# RiskChemi_Sensors_V2_10.net
KiCad netlist of a schematic drawn in Altium Designer
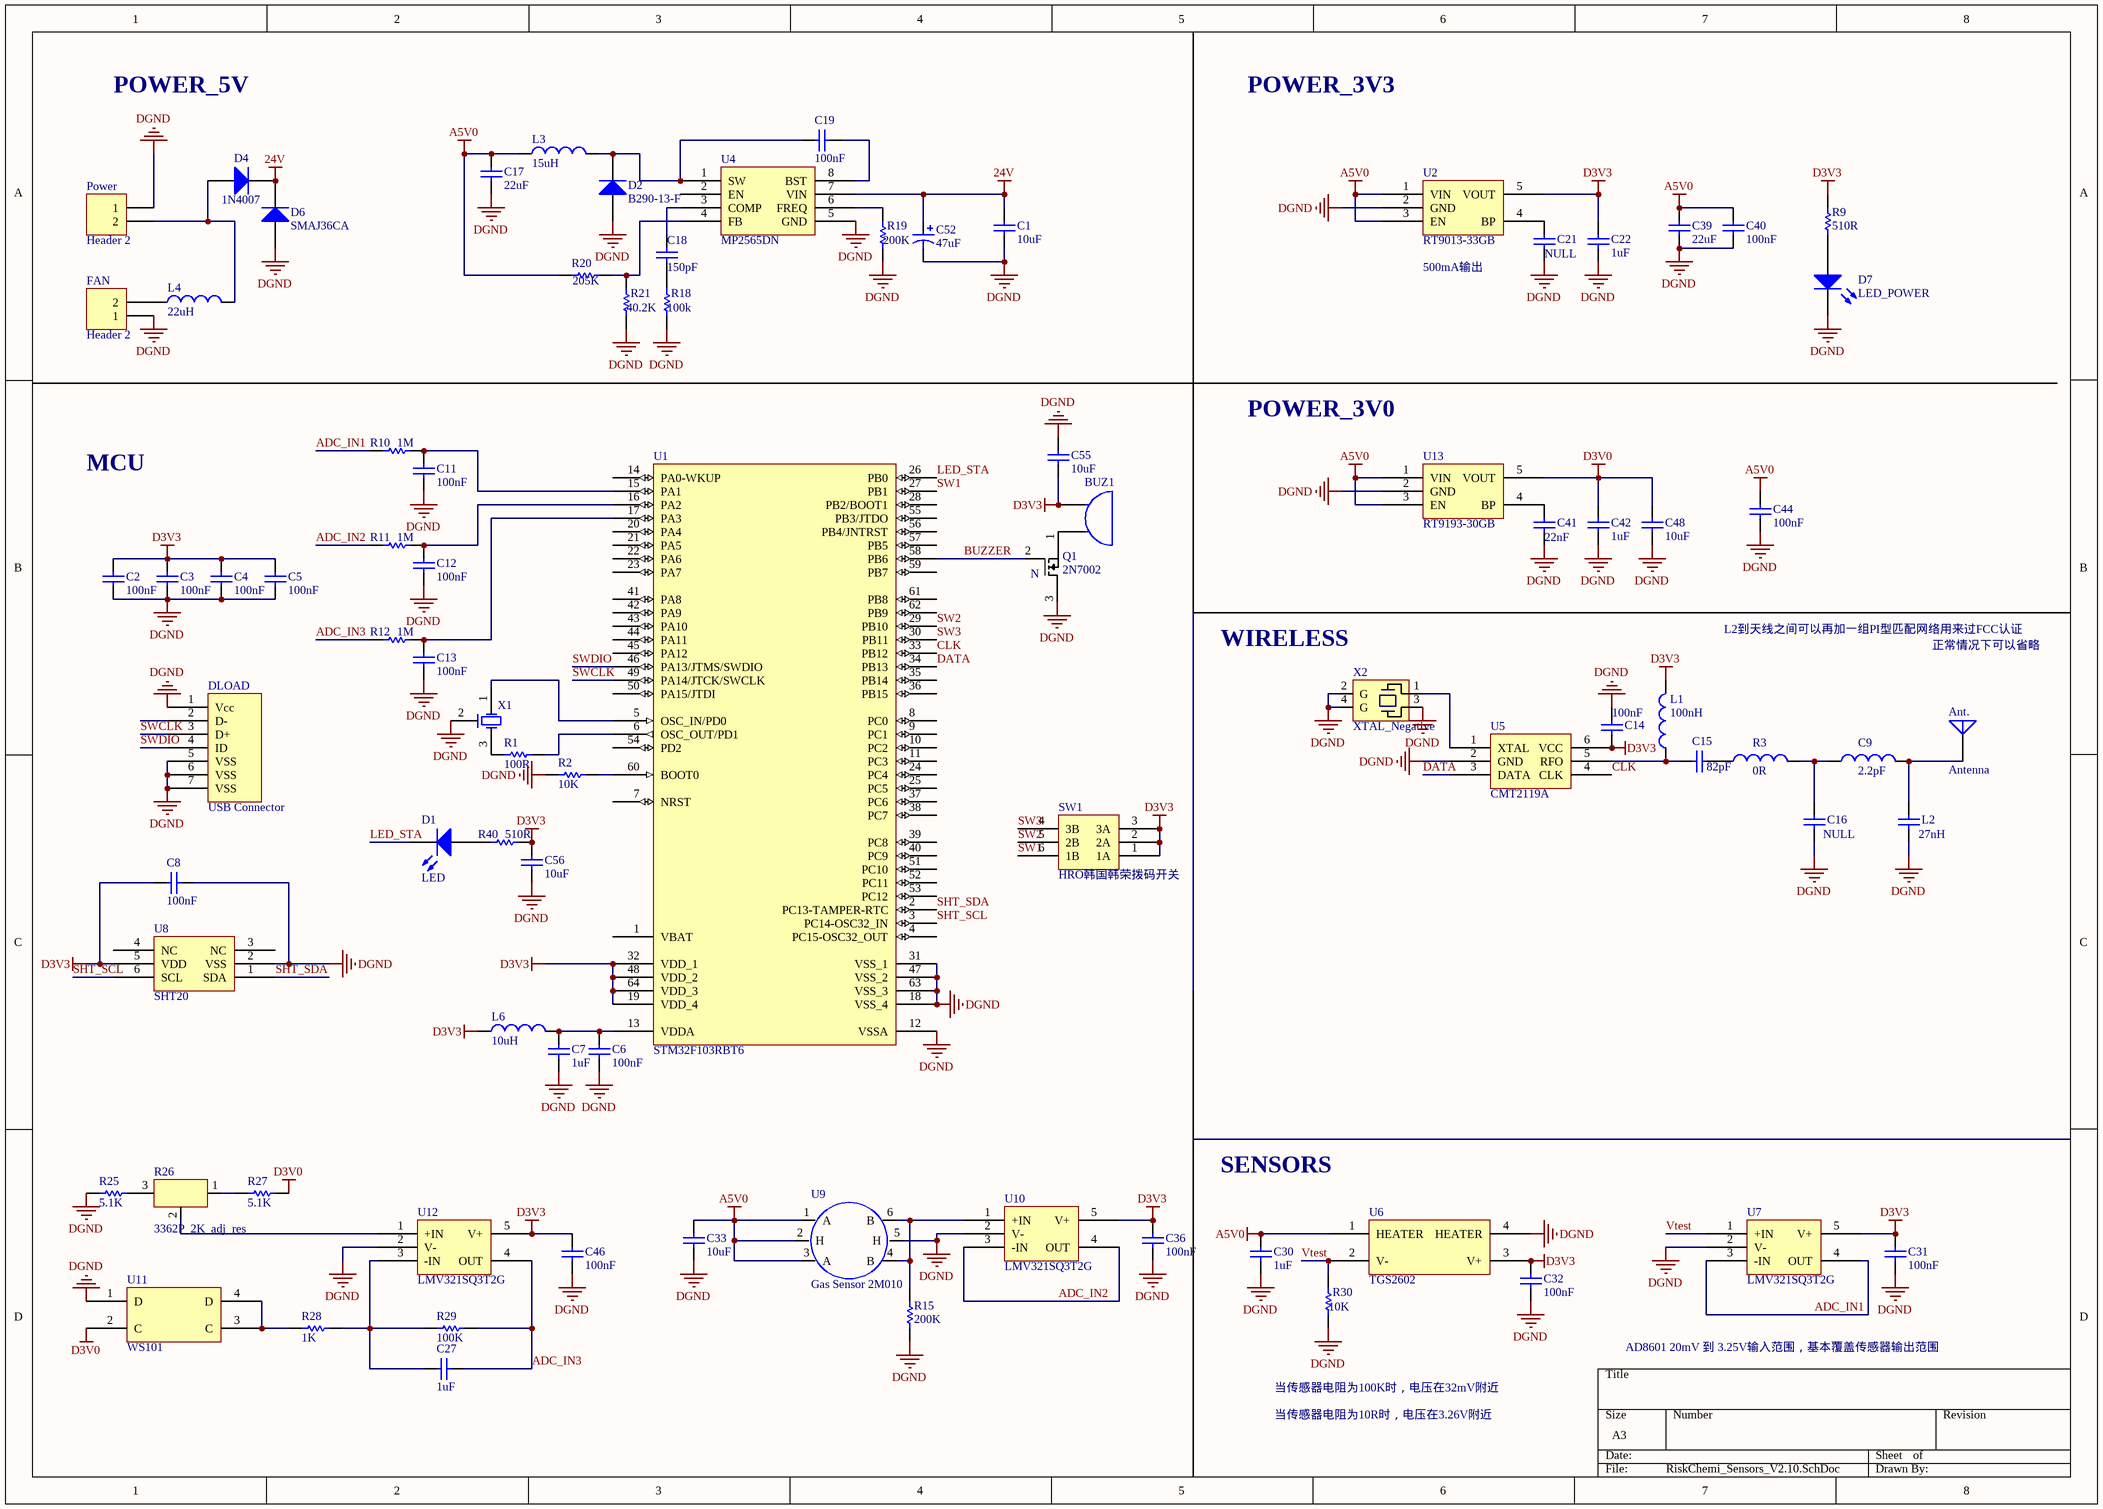
[diagram p0: RiskChemi_Sensors_V2.10.SchDoc]

(export (version "E")
  (design (tool "Eeschema 10.0.6"))
  (components
    (comp (ref "Ant.")
      (value "Antenna")
      (footprint "PIN1")
      (description "Generic Antenna")
      (fields (field (name "PUBLISHER") "Altium Limited"))
      (libsource (lib "Miscellaneous Devices") (part "Antenna"))
    )
    (comp (ref "BUZ1")
      (value "BUZZER 0905 through hole")
      (footprint "BUZ0905")
      (description "Buzzer")
      (libsource (lib "杂元件库") (part "BUZZER"))
    )
    (comp (ref "C1")
      (value "10uF")
      (footprint "0805")
      (description "Capacitor,50V")
      (fields (field (name "PUBLISHER") "Altium Limited"))
      (libsource (lib "Miscellaneous Devices") (part "Cap"))
    )
    (comp (ref "C2")
      (value "100nF")
      (footprint "BinFeng:0603")
      (description "Capacitor")
      (fields (field (name "PUBLISHER") "Altium Limited"))
      (libsource (lib "Miscellaneous Devices") (part "Cap"))
    )
    (comp (ref "C3")
      (value "100nF")
      (footprint "BinFeng:0603")
      (description "Capacitor")
      (fields (field (name "PUBLISHER") "Altium Limited"))
      (libsource (lib "Miscellaneous Devices") (part "Cap"))
    )
    (comp (ref "C4")
      (value "100nF")
      (footprint "BinFeng:0603")
      (description "Capacitor")
      (fields (field (name "PUBLISHER") "Altium Limited"))
      (libsource (lib "Miscellaneous Devices") (part "Cap"))
    )
    (comp (ref "C5")
      (value "100nF")
      (footprint "BinFeng:0603")
      (description "Capacitor")
      (fields (field (name "PUBLISHER") "Altium Limited"))
      (libsource (lib "Miscellaneous Devices") (part "Cap"))
    )
    (comp (ref "C6")
      (value "100nF")
      (footprint "BinFeng:0603")
      (description "Capacitor")
      (fields (field (name "PUBLISHER") "Altium Limited"))
      (libsource (lib "Miscellaneous Devices") (part "Cap"))
    )
    (comp (ref "C7")
      (value "1uF")
      (footprint "BinFeng:0603")
      (description "Capacitor")
      (fields (field (name "PUBLISHER") "Altium Limited"))
      (libsource (lib "Miscellaneous Devices") (part "Cap"))
    )
    (comp (ref "C8")
      (value "100nF")
      (footprint "BinFeng:0603")
      (description "Capacitor")
      (fields (field (name "PUBLISHER") "Altium Limited"))
      (libsource (lib "Miscellaneous Devices") (part "Cap"))
    )
    (comp (ref "C9")
      (value "2.2pF")
      (footprint "0603C")
      (description "Inductor")
      (fields (field (name "PUBLISHER") "Altium Limited"))
      (libsource (lib "Miscellaneous Devices") (part "Inductor"))
    )
    (comp (ref "C11")
      (value "100nF")
      (footprint "BinFeng:0603")
      (description "Capacitor")
      (fields (field (name "PUBLISHER") "Altium Limited"))
      (libsource (lib "Miscellaneous Devices") (part "Cap"))
    )
    (comp (ref "C12")
      (value "100nF")
      (footprint "BinFeng:0603")
      (description "Capacitor")
      (fields (field (name "PUBLISHER") "Altium Limited"))
      (libsource (lib "Miscellaneous Devices") (part "Cap"))
    )
    (comp (ref "C13")
      (value "100nF")
      (footprint "BinFeng:0603")
      (description "Capacitor")
      (fields (field (name "PUBLISHER") "Altium Limited"))
      (libsource (lib "Miscellaneous Devices") (part "Cap"))
    )
    (comp (ref "C14")
      (value "100nF")
      (footprint "BinFeng:0402")
      (description "Capacitor")
      (fields (field (name "PUBLISHER") "Altium Limited"))
      (libsource (lib "Miscellaneous Devices") (part "Cap"))
    )
    (comp (ref "C15")
      (value "82pF")
      (footprint "BinFeng:0402")
      (description "Capacitor")
      (fields (field (name "PUBLISHER") "Altium Limited"))
      (libsource (lib "Miscellaneous Devices") (part "Cap"))
    )
    (comp (ref "C16")
      (value "NULL")
      (footprint "BinFeng:0402")
      (description "Capacitor")
      (fields (field (name "PUBLISHER") "Altium Limited"))
      (libsource (lib "Miscellaneous Devices") (part "Cap"))
    )
    (comp (ref "C17")
      (value "22uF")
      (footprint "0805")
      (description "Capacitor,50V")
      (fields (field (name "PUBLISHER") "Altium Limited"))
      (libsource (lib "Miscellaneous Devices") (part "Cap"))
    )
    (comp (ref "C18")
      (value "150pF")
      (footprint "BinFeng:0603")
      (description "Capacitor")
      (fields (field (name "PUBLISHER") "Altium Limited"))
      (libsource (lib "Miscellaneous Devices") (part "Cap"))
    )
    (comp (ref "C19")
      (value "100nF")
      (footprint "BinFeng:0603")
      (description "Capacitor")
      (fields (field (name "PUBLISHER") "Altium Limited"))
      (libsource (lib "Miscellaneous Devices") (part "Cap"))
    )
    (comp (ref "C21")
      (value "NULL")
      (footprint "BinFeng:0402")
      (description "Capacitor")
      (fields (field (name "PUBLISHER") "Altium Limited"))
      (libsource (lib "Miscellaneous Devices") (part "Cap"))
    )
    (comp (ref "C22")
      (value "1uF")
      (footprint "BinFeng:0402")
      (description "Capacitor")
      (fields (field (name "PUBLISHER") "Altium Limited"))
      (libsource (lib "Miscellaneous Devices") (part "Cap"))
    )
    (comp (ref "C27")
      (value "1uF")
      (footprint "BinFeng:0603")
      (description "Capacitor")
      (fields (field (name "PUBLISHER") "Altium Limited"))
      (libsource (lib "Miscellaneous Devices") (part "Cap"))
    )
    (comp (ref "C30")
      (value "1uF")
      (footprint "BinFeng:0603")
      (description "Capacitor")
      (fields (field (name "PUBLISHER") "Altium Limited"))
      (libsource (lib "Miscellaneous Devices") (part "Cap"))
    )
    (comp (ref "C31")
      (value "100nF")
      (footprint "BinFeng:0603")
      (description "Capacitor")
      (fields (field (name "PUBLISHER") "Altium Limited"))
      (libsource (lib "Miscellaneous Devices") (part "Cap"))
    )
    (comp (ref "C32")
      (value "100nF")
      (footprint "BinFeng:0603")
      (description "Capacitor")
      (fields (field (name "PUBLISHER") "Altium Limited"))
      (libsource (lib "Miscellaneous Devices") (part "Cap"))
    )
    (comp (ref "C33")
      (value "10uF")
      (footprint "0805")
      (description "Capacitor")
      (fields (field (name "PUBLISHER") "Altium Limited"))
      (libsource (lib "Miscellaneous Devices") (part "Cap"))
    )
    (comp (ref "C36")
      (value "100nF")
      (footprint "BinFeng:0603")
      (description "Capacitor")
      (fields (field (name "PUBLISHER") "Altium Limited"))
      (libsource (lib "Miscellaneous Devices") (part "Cap"))
    )
    (comp (ref "C39")
      (value "22uF")
      (footprint "1206")
      (description "Capacitor")
      (fields (field (name "PUBLISHER") "Altium Limited"))
      (libsource (lib "Miscellaneous Devices") (part "Cap"))
    )
    (comp (ref "C40")
      (value "100nF")
      (footprint "BinFeng:0402")
      (description "Capacitor")
      (fields (field (name "PUBLISHER") "Altium Limited"))
      (libsource (lib "Miscellaneous Devices") (part "Cap"))
    )
    (comp (ref "C41")
      (value "22nF")
      (footprint "BinFeng:0402")
      (description "Capacitor")
      (fields (field (name "PUBLISHER") "Altium Limited"))
      (libsource (lib "Miscellaneous Devices") (part "Cap"))
    )
    (comp (ref "C42")
      (value "1uF")
      (footprint "BinFeng:0402")
      (description "Capacitor")
      (fields (field (name "PUBLISHER") "Altium Limited"))
      (libsource (lib "Miscellaneous Devices") (part "Cap"))
    )
    (comp (ref "C44")
      (value "100nF")
      (footprint "BinFeng:0402")
      (description "Capacitor")
      (fields (field (name "PUBLISHER") "Altium Limited"))
      (libsource (lib "Miscellaneous Devices") (part "Cap"))
    )
    (comp (ref "C46")
      (value "100nF")
      (footprint "BinFeng:0603")
      (description "Capacitor")
      (fields (field (name "PUBLISHER") "Altium Limited"))
      (libsource (lib "Miscellaneous Devices") (part "Cap"))
    )
    (comp (ref "C48")
      (value "10uF")
      (footprint "0805")
      (description "Capacitor")
      (fields (field (name "PUBLISHER") "Altium Limited"))
      (libsource (lib "Miscellaneous Devices") (part "Cap"))
    )
    (comp (ref "C52")
      (value "47uF")
      (footprint "cap_pol_8*10.2")
      (description "Polarized Capacitor (Radial)")
      (fields (field (name "PUBLISHER") "Altium Limited"))
      (libsource (lib "Miscellaneous Devices") (part "Cap Pol1"))
    )
    (comp (ref "C55")
      (value "10uF")
      (footprint "0805")
      (description "Capacitor")
      (fields (field (name "PUBLISHER") "Altium Limited"))
      (libsource (lib "Miscellaneous Devices") (part "Cap"))
    )
    (comp (ref "C56")
      (value "10uF")
      (footprint "0805")
      (description "Capacitor")
      (fields (field (name "PUBLISHER") "Altium Limited"))
      (libsource (lib "Miscellaneous Devices") (part "Cap"))
    )
    (comp (ref "D1")
      (value "LED")
      (footprint "1206_LED")
      (description "Typical INFRARED GaAs LED")
      (fields (field (name "PUBLISHER") "Altium Limited"))
      (libsource (lib "Miscellaneous Devices") (part "LED0"))
    )
    (comp (ref "D2")
      (value "B290-13-F")
      (footprint "B290")
      (description "Default Diode")
      (fields (field (name "PUBLISHER") "Altium Limited"))
      (libsource (lib "Miscellaneous Devices") (part "Diode"))
    )
    (comp (ref "D4")
      (value "1N4007")
      (footprint "6032_pol")
      (description "1 Amp General Purpose Rectifier")
      (fields (field (name "PUBLISHER") "Altium Limited"))
      (libsource (lib "Miscellaneous Devices") (part "Diode 1N4007"))
    )
    (comp (ref "D6")
      (value "SMAJ36CA")
      (footprint "B290")
      (description "1 Amp General Purpose Rectifier")
      (fields (field (name "PUBLISHER") "Altium Limited"))
      (libsource (lib "Miscellaneous Devices") (part "Diode 1N4007"))
    )
    (comp (ref "D7")
      (value "LED_POWER")
      (footprint "1206_LED")
      (description "Typical INFRARED GaAs LED")
      (fields (field (name "PUBLISHER") "Altium Limited"))
      (libsource (lib "Miscellaneous Devices") (part "LED0"))
    )
    (comp (ref "DLOAD")
      (value "USB Connector")
      (footprint "Mini_USB")
      (libsource (lib "BinFeng_Connectors") (part "Component_1"))
    )
    (comp (ref "FAN")
      (value "Header 2")
      (footprint "HDR1X2")
      (description "Header, 2-Pin")
      (fields (field (name "PUBLISHER") "Altium Limited"))
      (libsource (lib "Miscellaneous Connectors") (part "Header 2"))
    )
    (comp (ref "L1")
      (value "100nH")
      (footprint "0603C")
      (description "Inductor")
      (fields (field (name "PUBLISHER") "Altium Limited"))
      (libsource (lib "Miscellaneous Devices") (part "Inductor"))
    )
    (comp (ref "L2")
      (value "27nH")
      (footprint "BinFeng:0402")
      (description "Capacitor")
      (fields (field (name "PUBLISHER") "Altium Limited"))
      (libsource (lib "Miscellaneous Devices") (part "Cap"))
    )
    (comp (ref "L3")
      (value "15uH")
      (footprint "4*4 Inductor")
      (description "Inductor, 1A")
      (fields (field (name "PUBLISHER") "Altium Limited"))
      (libsource (lib "Miscellaneous Devices") (part "Inductor"))
    )
    (comp (ref "L4")
      (value "22uH")
      (footprint "10*10Inductor")
      (description "Inductor, 1A")
      (fields (field (name "PUBLISHER") "Altium Limited"))
      (libsource (lib "Miscellaneous Devices") (part "Inductor"))
    )
    (comp (ref "L6")
      (value "10uH")
      (footprint "0805")
      (description "Inductor")
      (fields (field (name "PUBLISHER") "Altium Limited"))
      (libsource (lib "Miscellaneous Devices") (part "Inductor"))
    )
    (comp (ref "Power")
      (value "Header 2")
      (footprint "HDR1X2")
      (description "Header, 2-Pin")
      (fields (field (name "PUBLISHER") "Altium Limited"))
      (libsource (lib "") (part "Header 2_1"))
    )
    (comp (ref "Q1") (value "2N7002") (footprint "2N7002") (libsource (lib "seeder") (part "N-MOSFET")))
    (comp (ref "R1")
      (value "100R")
      (footprint "BinFeng:0603")
      (description "Resistor")
      (fields (field (name "PUBLISHER") "Altium Limited"))
      (libsource (lib "Miscellaneous Devices") (part "Res1"))
    )
    (comp (ref "R2")
      (value "10K")
      (footprint "BinFeng:0603")
      (description "Resistor")
      (fields (field (name "PUBLISHER") "Altium Limited"))
      (libsource (lib "Miscellaneous Devices") (part "Res1"))
    )
    (comp (ref "R3")
      (value "0R")
      (footprint "0603C")
      (description "Inductor")
      (fields (field (name "PUBLISHER") "Altium Limited"))
      (libsource (lib "Miscellaneous Devices") (part "Inductor"))
    )
    (comp (ref "R9")
      (value "510R")
      (footprint "BinFeng:0603")
      (description "Resistor")
      (fields (field (name "PUBLISHER") "Altium Limited"))
      (libsource (lib "Miscellaneous Devices") (part "Res1"))
    )
    (comp (ref "R10")
      (value "1M")
      (footprint "BinFeng:0603")
      (description "Resistor")
      (fields (field (name "PUBLISHER") "Altium Limited"))
      (libsource (lib "Miscellaneous Devices") (part "Res1"))
    )
    (comp (ref "R11")
      (value "1M")
      (footprint "BinFeng:0603")
      (description "Resistor")
      (fields (field (name "PUBLISHER") "Altium Limited"))
      (libsource (lib "Miscellaneous Devices") (part "Res1"))
    )
    (comp (ref "R12")
      (value "1M")
      (footprint "BinFeng:0603")
      (description "Resistor")
      (fields (field (name "PUBLISHER") "Altium Limited"))
      (libsource (lib "Miscellaneous Devices") (part "Res1"))
    )
    (comp (ref "R15")
      (value "200K")
      (footprint "BinFeng:0603C")
      (description "Resistor")
      (fields (field (name "Comment") "Res1") (field (name "PUBLISHER") "Altium Limited"))
      (libsource (lib "Miscellaneous Devices") (part "Res1"))
    )
    (comp (ref "R18")
      (value "100k")
      (footprint "BinFeng:0603")
      (description "Resistor")
      (fields (field (name "PUBLISHER") "Altium Limited"))
      (libsource (lib "Miscellaneous Devices") (part "Res1"))
    )
    (comp (ref "R19")
      (value "200K")
      (footprint "BinFeng:0402")
      (description "Resistor")
      (fields (field (name "PUBLISHER") "Altium Limited"))
      (libsource (lib "Miscellaneous Devices") (part "Res1"))
    )
    (comp (ref "R20")
      (value "205K")
      (footprint "BinFeng:0603")
      (description "Resistor")
      (fields (field (name "PUBLISHER") "Altium Limited"))
      (libsource (lib "Miscellaneous Devices") (part "Res1"))
    )
    (comp (ref "R21")
      (value "40.2K")
      (footprint "BinFeng:0603")
      (description "Resistor")
      (fields (field (name "PUBLISHER") "Altium Limited"))
      (libsource (lib "Miscellaneous Devices") (part "Res1"))
    )
    (comp (ref "R25")
      (value "5.1K")
      (footprint "BinFeng:0603")
      (description "Resistor")
      (fields (field (name "PUBLISHER") "Altium Limited"))
      (libsource (lib "Miscellaneous Devices") (part "Res1"))
    )
    (comp (ref "R26")
      (value "3362P_2K_adj_res")
      (footprint "res_adj")
      (libsource (lib "BinFeng_IC") (part "res_adj"))
    )
    (comp (ref "R27")
      (value "5.1K")
      (footprint "BinFeng:0603")
      (description "Resistor")
      (fields (field (name "PUBLISHER") "Altium Limited"))
      (libsource (lib "Miscellaneous Devices") (part "Res1"))
    )
    (comp (ref "R28")
      (value "1K")
      (footprint "BinFeng:0603")
      (description "Resistor")
      (fields (field (name "PUBLISHER") "Altium Limited"))
      (libsource (lib "Miscellaneous Devices") (part "Res1"))
    )
    (comp (ref "R29")
      (value "100K")
      (footprint "BinFeng:0603")
      (description "Resistor")
      (fields (field (name "PUBLISHER") "Altium Limited"))
      (libsource (lib "Miscellaneous Devices") (part "Res1"))
    )
    (comp (ref "R30")
      (value "10K")
      (footprint "BinFeng:0603")
      (description "Resistor")
      (fields (field (name "PUBLISHER") "Altium Limited"))
      (libsource (lib "Miscellaneous Devices") (part "Res1"))
    )
    (comp (ref "R40")
      (value "510R")
      (footprint "BinFeng:0603")
      (description "Resistor")
      (fields (field (name "PUBLISHER") "Altium Limited"))
      (libsource (lib "Miscellaneous Devices") (part "Res1"))
    )
    (comp (ref "SW1")
      (value "HRO韩国韩荣拨码开关")
      (footprint "SW_6P_HRO")
      (libsource (lib "BinFeng_IC") (part "SW_6P"))
    )
    (comp (ref "U1")
      (value "STM32F103RBT6")
      (footprint "LQFP64_N")
      (description "STM32 ARM-based 32-bit MCU with 64 Kbytes Flash, 64-pin LQFP, Industrial Temperature")
      (fields (field (name "PUBLISHER") "Altium Limited"))
      (libsource (lib "ST Microcontroller 32-Bit STM32") (part "STM32F103R8T6"))
    )
    (comp (ref "U2")
      (value "RT9013-33GB")
      (footprint "SOT-23-5")
      (libsource (lib "BinFeng_IC") (part "RT9193"))
    )
    (comp (ref "U4")
      (value "MP2565DN")
      (footprint "so-8")
      (description "DCDC 4.5V~28V input 1.8V ~5V output low power")
      (libsource (lib "BinFeng_IC") (part "MP1584"))
    )
    (comp (ref "U5")
      (value "CMT2119A")
      (footprint "sot23-6")
      (libsource (lib "BinFeng_IC") (part "CMT2119A"))
    )
    (comp (ref "U6")
      (value "TGS2602")
      (footprint "Gas Sensor TGS2602 Slot")
      (description "VOC sensor")
      (libsource (lib "BinFeng_IC") (part "TGS2602"))
    )
    (comp (ref "U7")
      (value "LMV321SQ3T2G")
      (footprint "SC-70-5")
      (libsource (lib "BinFeng_IC") (part "LMV321SQ3T2G"))
    )
    (comp (ref "U8") (value "SHT20") (footprint "SHT20") (libsource (lib "BinFeng_IC") (part "SHT20")))
    (comp (ref "U9")
      (value "Gas Sensor 2M010")
      (footprint "Gas Sensor 2M010 Slot")
      (libsource (lib "BinFeng_IC") (part "Gas Sensor"))
    )
    (comp (ref "U10")
      (value "LMV321SQ3T2G")
      (footprint "SC-70-5")
      (libsource (lib "BinFeng_IC") (part "LMV321SQ3T2G"))
    )
    (comp (ref "U11")
      (value "WS101")
      (footprint "Gas_Sensor_WS101_Slot")
      (libsource (lib "BinFeng_IC") (part "Gas Sensor_WS101"))
    )
    (comp (ref "U12")
      (value "LMV321SQ3T2G")
      (footprint "SC-70-5")
      (libsource (lib "BinFeng_IC") (part "LMV321SQ3T2G"))
    )
    (comp (ref "U13")
      (value "RT9193-30GB")
      (footprint "SOT-23-5")
      (libsource (lib "BinFeng_IC") (part "RT9193"))
    )
    (comp (ref "X1") (value "8M smd") (footprint "8Mhz_XTAL") (libsource (lib "Schlib1") (part "8M smd")))
    (comp (ref "X2")
      (value "XTAL_Negative")
      (footprint "XTAL3225")
      (libsource (lib "BinFeng_IC") (part "XTAL_Negative"))
    )
  )
  (nets
    (net (code "1") (name "/ADC_IN1") (class "Default")
      (node (ref "R10") (pin "1") (pinfunction "1_1") (pintype "passive"))
      (node (ref "U7") (pin "3") (pinfunction "-IN_3") (pintype "passive"))
      (node (ref "U7") (pin "4") (pinfunction "OUT_4") (pintype "passive"))
    )
    (net (code "2") (name "/ADC_IN2") (class "Default")
      (node (ref "R11") (pin "1") (pinfunction "1_1") (pintype "passive"))
      (node (ref "U10") (pin "3") (pinfunction "-IN_3") (pintype "passive"))
      (node (ref "U10") (pin "4") (pinfunction "OUT_4") (pintype "passive"))
    )
    (net (code "3") (name "/ADC_IN3") (class "Default")
      (node (ref "C27") (pin "1") (pinfunction "1_1") (pintype "passive"))
      (node (ref "R12") (pin "1") (pinfunction "1_1") (pintype "passive"))
      (node (ref "R29") (pin "2") (pinfunction "2_2") (pintype "passive"))
      (node (ref "U12") (pin "4") (pinfunction "OUT_4") (pintype "passive"))
    )
    (net (code "4") (name "/BUZZER") (class "Default")
      (node (ref "Q1") (pin "2") (pinfunction "G_2") (pintype "passive"))
      (node (ref "U1") (pin "58") (pinfunction "PB6_58") (pintype "bidirectional"))
    )
    (net (code "5") (name "/CLK") (class "Default")
      (node (ref "U1") (pin "33") (pinfunction "PB12_33") (pintype "bidirectional"))
      (node (ref "U5") (pin "4") (pinfunction "CLK_4") (pintype "passive"))
    )
    (net (code "6") (name "/DATA") (class "Default")
      (node (ref "U1") (pin "34") (pinfunction "PB13_34") (pintype "bidirectional"))
      (node (ref "U5") (pin "3") (pinfunction "DATA_3") (pintype "passive"))
    )
    (net (code "7") (name "/LED_STA") (class "Default")
      (node (ref "D1") (pin "2") (pinfunction "K_2") (pintype "passive"))
      (node (ref "U1") (pin "26") (pinfunction "PB0_26") (pintype "bidirectional"))
    )
    (net (code "8") (name "/SHT_SCL") (class "Default")
      (node (ref "U1") (pin "3") (pinfunction "PC14-OSC32_IN_3") (pintype "bidirectional"))
      (node (ref "U8") (pin "6") (pinfunction "SCL_6") (pintype "passive"))
    )
    (net (code "9") (name "/SHT_SDA") (class "Default")
      (node (ref "U1") (pin "2") (pinfunction "PC13-TAMPER-RTC_2") (pintype "bidirectional"))
      (node (ref "U8") (pin "1") (pinfunction "SDA_1") (pintype "passive"))
    )
    (net (code "10") (name "/SW1") (class "Default")
      (node (ref "SW1") (pin "6") (pinfunction "1B_6") (pintype "passive"))
      (node (ref "U1") (pin "27") (pinfunction "PB1_27") (pintype "bidirectional"))
    )
    (net (code "11") (name "/SW2") (class "Default")
      (node (ref "SW1") (pin "5") (pinfunction "2B_5") (pintype "passive"))
      (node (ref "U1") (pin "29") (pinfunction "PB10_29") (pintype "bidirectional"))
    )
    (net (code "12") (name "/SW3") (class "Default")
      (node (ref "SW1") (pin "4") (pinfunction "3B_4") (pintype "passive"))
      (node (ref "U1") (pin "30") (pinfunction "PB11_30") (pintype "bidirectional"))
    )
    (net (code "13") (name "/SWCLK") (class "Default")
      (node (ref "DLOAD") (pin "3") (pinfunction "D+_3") (pintype "passive"))
      (node (ref "U1") (pin "49") (pinfunction "PA14/JTCK/SWCLK_49") (pintype "bidirectional"))
    )
    (net (code "14") (name "/SWDIO") (class "Default")
      (node (ref "DLOAD") (pin "4") (pinfunction "ID_4") (pintype "passive"))
      (node (ref "U1") (pin "46") (pinfunction "PA13/JTMS/SWDIO_46") (pintype "bidirectional"))
    )
    (net (code "15") (name "/Vtest") (class "Default")
      (node (ref "R30") (pin "2") (pinfunction "2_2") (pintype "passive"))
      (node (ref "U6") (pin "2") (pinfunction "V-_2") (pintype "passive"))
      (node (ref "U7") (pin "1") (pinfunction "+IN_1") (pintype "passive"))
    )
    (net (code "16") (name "24V") (class "Default")
      (node (ref "C1") (pin "2") (pinfunction "2_2") (pintype "passive"))
      (node (ref "C52") (pin "1") (pinfunction "1_1") (pintype "passive"))
      (node (ref "D4") (pin "2") (pinfunction "K_2") (pintype "passive"))
      (node (ref "D6") (pin "2") (pinfunction "K_2") (pintype "passive"))
      (node (ref "U4") (pin "7") (pinfunction "VIN_7") (pintype "passive"))
    )
    (net (code "17") (name "A5V0") (class "Default")
      (node (ref "C17") (pin "2") (pinfunction "2_2") (pintype "passive"))
      (node (ref "C30") (pin "2") (pinfunction "2_2") (pintype "passive"))
      (node (ref "C33") (pin "2") (pinfunction "2_2") (pintype "passive"))
      (node (ref "C39") (pin "1") (pinfunction "1_1") (pintype "passive"))
      (node (ref "C40") (pin "2") (pinfunction "2_2") (pintype "passive"))
      (node (ref "C44") (pin "2") (pinfunction "2_2") (pintype "passive"))
      (node (ref "L3") (pin "1") (pinfunction "1_1") (pintype "passive"))
      (node (ref "R20") (pin "2") (pinfunction "2_2") (pintype "passive"))
      (node (ref "U13") (pin "1") (pinfunction "VIN_1") (pintype "passive"))
      (node (ref "U13") (pin "3") (pinfunction "EN_3") (pintype "passive"))
      (node (ref "U2") (pin "1") (pinfunction "VIN_1") (pintype "passive"))
      (node (ref "U2") (pin "3") (pinfunction "EN_3") (pintype "passive"))
      (node (ref "U6") (pin "1") (pinfunction "HEATER_1") (pintype "passive"))
      (node (ref "U9") (pin "1") (pinfunction "A_1") (pintype "passive"))
      (node (ref "U9") (pin "2") (pinfunction "H_2") (pintype "passive"))
      (node (ref "U9") (pin "3") (pinfunction "A_3") (pintype "passive"))
    )
    (net (code "18") (name "D3V0") (class "Default")
      (node (ref "C42") (pin "2") (pinfunction "2_2") (pintype "passive"))
      (node (ref "C48") (pin "2") (pinfunction "2_2") (pintype "passive"))
      (node (ref "R27") (pin "2") (pinfunction "2_2") (pintype "passive"))
      (node (ref "U11") (pin "2") (pinfunction "C_2") (pintype "passive"))
      (node (ref "U13") (pin "5") (pinfunction "VOUT_5") (pintype "passive"))
    )
    (net (code "19") (name "D3V3") (class "Default")
      (node (ref "BUZ1") (pin "1") (pinfunction "A_1") (pintype "passive"))
      (node (ref "C14") (pin "2") (pinfunction "2_2") (pintype "passive"))
      (node (ref "C2") (pin "2") (pinfunction "2_2") (pintype "passive"))
      (node (ref "C22") (pin "2") (pinfunction "2_2") (pintype "passive"))
      (node (ref "C3") (pin "2") (pinfunction "2_2") (pintype "passive"))
      (node (ref "C31") (pin "2") (pinfunction "2_2") (pintype "passive"))
      (node (ref "C32") (pin "2") (pinfunction "2_2") (pintype "passive"))
      (node (ref "C36") (pin "2") (pinfunction "2_2") (pintype "passive"))
      (node (ref "C4") (pin "2") (pinfunction "2_2") (pintype "passive"))
      (node (ref "C46") (pin "2") (pinfunction "2_2") (pintype "passive"))
      (node (ref "C5") (pin "2") (pinfunction "2_2") (pintype "passive"))
      (node (ref "C55") (pin "2") (pinfunction "2_2") (pintype "passive"))
      (node (ref "C56") (pin "2") (pinfunction "2_2") (pintype "passive"))
      (node (ref "C8") (pin "2") (pinfunction "2_2") (pintype "passive"))
      (node (ref "L1") (pin "2") (pinfunction "2_2") (pintype "passive"))
      (node (ref "L6") (pin "1") (pinfunction "1_1") (pintype "passive"))
      (node (ref "R40") (pin "2") (pinfunction "2_2") (pintype "passive"))
      (node (ref "R9") (pin "2") (pinfunction "2_2") (pintype "passive"))
      (node (ref "SW1") (pin "1") (pinfunction "1A_1") (pintype "passive"))
      (node (ref "SW1") (pin "2") (pinfunction "2A_2") (pintype "passive"))
      (node (ref "SW1") (pin "3") (pinfunction "3A_3") (pintype "passive"))
      (node (ref "U1") (pin "19") (pinfunction "VDD_4_19") (pintype "power_in"))
      (node (ref "U1") (pin "32") (pinfunction "VDD_1_32") (pintype "power_in"))
      (node (ref "U1") (pin "48") (pinfunction "VDD_2_48") (pintype "power_in"))
      (node (ref "U1") (pin "64") (pinfunction "VDD_3_64") (pintype "power_in"))
      (node (ref "U10") (pin "5") (pinfunction "V+_5") (pintype "passive"))
      (node (ref "U12") (pin "5") (pinfunction "V+_5") (pintype "passive"))
      (node (ref "U2") (pin "5") (pinfunction "VOUT_5") (pintype "passive"))
      (node (ref "U5") (pin "6") (pinfunction "VCC_6") (pintype "passive"))
      (node (ref "U6") (pin "3") (pinfunction "V+_3") (pintype "passive"))
      (node (ref "U7") (pin "5") (pinfunction "V+_5") (pintype "passive"))
      (node (ref "U8") (pin "5") (pinfunction "VDD_5") (pintype "passive"))
    )
    (net (code "20") (name "DGND") (class "Default")
      (node (ref "C1") (pin "1") (pinfunction "1_1") (pintype "passive"))
      (node (ref "C11") (pin "2") (pinfunction "2_2") (pintype "passive"))
      (node (ref "C12") (pin "1") (pinfunction "1_1") (pintype "passive"))
      (node (ref "C13") (pin "1") (pinfunction "1_1") (pintype "passive"))
      (node (ref "C14") (pin "1") (pinfunction "1_1") (pintype "passive"))
      (node (ref "C16") (pin "1") (pinfunction "1_1") (pintype "passive"))
      (node (ref "C17") (pin "1") (pinfunction "1_1") (pintype "passive"))
      (node (ref "C2") (pin "1") (pinfunction "1_1") (pintype "passive"))
      (node (ref "C21") (pin "1") (pinfunction "1_1") (pintype "passive"))
      (node (ref "C22") (pin "1") (pinfunction "1_1") (pintype "passive"))
      (node (ref "C3") (pin "1") (pinfunction "1_1") (pintype "passive"))
      (node (ref "C30") (pin "1") (pinfunction "1_1") (pintype "passive"))
      (node (ref "C31") (pin "1") (pinfunction "1_1") (pintype "passive"))
      (node (ref "C32") (pin "1") (pinfunction "1_1") (pintype "passive"))
      (node (ref "C33") (pin "1") (pinfunction "1_1") (pintype "passive"))
      (node (ref "C36") (pin "1") (pinfunction "1_1") (pintype "passive"))
      (node (ref "C39") (pin "2") (pinfunction "2_2") (pintype "passive"))
      (node (ref "C4") (pin "1") (pinfunction "1_1") (pintype "passive"))
      (node (ref "C40") (pin "1") (pinfunction "1_1") (pintype "passive"))
      (node (ref "C41") (pin "1") (pinfunction "1_1") (pintype "passive"))
      (node (ref "C42") (pin "1") (pinfunction "1_1") (pintype "passive"))
      (node (ref "C44") (pin "1") (pinfunction "1_1") (pintype "passive"))
      (node (ref "C46") (pin "1") (pinfunction "1_1") (pintype "passive"))
      (node (ref "C48") (pin "1") (pinfunction "1_1") (pintype "passive"))
      (node (ref "C5") (pin "1") (pinfunction "1_1") (pintype "passive"))
      (node (ref "C52") (pin "2") (pinfunction "2_2") (pintype "passive"))
      (node (ref "C55") (pin "1") (pinfunction "1_1") (pintype "passive"))
      (node (ref "C56") (pin "1") (pinfunction "1_1") (pintype "passive"))
      (node (ref "C6") (pin "1") (pinfunction "1_1") (pintype "passive"))
      (node (ref "C7") (pin "1") (pinfunction "1_1") (pintype "passive"))
      (node (ref "C8") (pin "1") (pinfunction "1_1") (pintype "passive"))
      (node (ref "D2") (pin "1") (pinfunction "A_1") (pintype "passive"))
      (node (ref "D6") (pin "1") (pinfunction "A_1") (pintype "passive"))
      (node (ref "D7") (pin "2") (pinfunction "K_2") (pintype "passive"))
      (node (ref "DLOAD") (pin "1") (pinfunction "Vcc_1") (pintype "passive"))
      (node (ref "DLOAD") (pin "5") (pinfunction "VSS_5") (pintype "passive"))
      (node (ref "DLOAD") (pin "6") (pinfunction "VSS_6") (pintype "passive"))
      (node (ref "DLOAD") (pin "7") (pinfunction "VSS_7") (pintype "passive"))
      (node (ref "FAN") (pin "1") (pinfunction "1_1") (pintype "passive"))
      (node (ref "L2") (pin "1") (pinfunction "1_1") (pintype "passive"))
      (node (ref "Power") (pin "1") (pinfunction "1_1") (pintype "passive"))
      (node (ref "Q1") (pin "3") (pinfunction "S_3") (pintype "passive"))
      (node (ref "R15") (pin "2") (pinfunction "2_2") (pintype "passive"))
      (node (ref "R18") (pin "1") (pinfunction "1_1") (pintype "passive"))
      (node (ref "R19") (pin "1") (pinfunction "1_1") (pintype "passive"))
      (node (ref "R2") (pin "1") (pinfunction "1_1") (pintype "passive"))
      (node (ref "R21") (pin "1") (pinfunction "1_1") (pintype "passive"))
      (node (ref "R25") (pin "1") (pinfunction "1_1") (pintype "passive"))
      (node (ref "R30") (pin "1") (pinfunction "1_1") (pintype "passive"))
      (node (ref "U1") (pin "12") (pinfunction "VSSA_12") (pintype "power_in"))
      (node (ref "U1") (pin "18") (pinfunction "VSS_4_18") (pintype "power_in"))
      (node (ref "U1") (pin "31") (pinfunction "VSS_1_31") (pintype "power_in"))
      (node (ref "U1") (pin "47") (pinfunction "VSS_2_47") (pintype "power_in"))
      (node (ref "U1") (pin "63") (pinfunction "VSS_3_63") (pintype "power_in"))
      (node (ref "U10") (pin "2") (pinfunction "V-_2") (pintype "passive"))
      (node (ref "U11") (pin "1") (pinfunction "D_1") (pintype "passive"))
      (node (ref "U12") (pin "2") (pinfunction "V-_2") (pintype "passive"))
      (node (ref "U13") (pin "2") (pinfunction "GND_2") (pintype "passive"))
      (node (ref "U2") (pin "2") (pinfunction "GND_2") (pintype "passive"))
      (node (ref "U4") (pin "5") (pinfunction "GND_5") (pintype "passive"))
      (node (ref "U5") (pin "2") (pinfunction "GND_2") (pintype "passive"))
      (node (ref "U6") (pin "4") (pinfunction "HEATER_4") (pintype "passive"))
      (node (ref "U7") (pin "2") (pinfunction "V-_2") (pintype "passive"))
      (node (ref "U8") (pin "2") (pinfunction "VSS_2") (pintype "passive"))
      (node (ref "U9") (pin "5") (pinfunction "H_5") (pintype "passive"))
      (node (ref "X1") (pin "2") (pinfunction "GND_2") (pintype "passive"))
      (node (ref "X2") (pin "2") (pinfunction "G_2") (pintype "passive"))
      (node (ref "X2") (pin "3") (pintype "passive"))
      (node (ref "X2") (pin "4") (pinfunction "G_4") (pintype "passive"))
    )
    (net (code "21") (name "Net-(Ant.-A)") (class "Default")
      (node (ref "Ant.") (pin "1") (pinfunction "A_1") (pintype "passive"))
      (node (ref "C9") (pin "2") (pinfunction "2_2") (pintype "passive"))
      (node (ref "L2") (pin "2") (pinfunction "2_2") (pintype "passive"))
    )
    (net (code "22") (name "Net-(BUZ1-B)") (class "Default")
      (node (ref "BUZ1") (pin "2") (pinfunction "B_2") (pintype "passive"))
      (node (ref "Q1") (pin "1") (pinfunction "D_1") (pintype "passive"))
    )
    (net (code "23") (name "Net-(C15-Pad2)") (class "Default")
      (node (ref "C15") (pin "2") (pinfunction "2_2") (pintype "passive"))
      (node (ref "R3") (pin "1") (pinfunction "1_1") (pintype "passive"))
    )
    (net (code "24") (name "Net-(C16-Pad2)") (class "Default")
      (node (ref "C16") (pin "2") (pinfunction "2_2") (pintype "passive"))
      (node (ref "C9") (pin "1") (pinfunction "1_1") (pintype "passive"))
      (node (ref "R3") (pin "2") (pinfunction "2_2") (pintype "passive"))
    )
    (net (code "25") (name "Net-(C18-Pad2)") (class "Default")
      (node (ref "C18") (pin "2") (pinfunction "2_2") (pintype "passive"))
      (node (ref "R18") (pin "2") (pinfunction "2_2") (pintype "passive"))
    )
    (net (code "26") (name "Net-(D1-A)") (class "Default")
      (node (ref "D1") (pin "1") (pinfunction "A_1") (pintype "passive"))
      (node (ref "R40") (pin "1") (pinfunction "1_1") (pintype "passive"))
    )
    (net (code "27") (name "Net-(D2-K)") (class "Default")
      (node (ref "C19") (pin "2") (pinfunction "2_2") (pintype "passive"))
      (node (ref "D2") (pin "2") (pinfunction "K_2") (pintype "passive"))
      (node (ref "L3") (pin "2") (pinfunction "2_2") (pintype "passive"))
      (node (ref "U4") (pin "1") (pinfunction "SW_1") (pintype "passive"))
    )
    (net (code "28") (name "Net-(D4-A)") (class "Default")
      (node (ref "D4") (pin "1") (pinfunction "A_1") (pintype "passive"))
      (node (ref "L4") (pin "2") (pinfunction "2_2") (pintype "passive"))
      (node (ref "Power") (pin "2") (pinfunction "2_2") (pintype "passive"))
    )
    (net (code "29") (name "Net-(D7-A)") (class "Default")
      (node (ref "D7") (pin "1") (pinfunction "A_1") (pintype "passive"))
      (node (ref "R9") (pin "1") (pinfunction "1_1") (pintype "passive"))
    )
    (net (code "30") (name "Net-(FAN-Pad2)") (class "Default")
      (node (ref "FAN") (pin "2") (pinfunction "2_2") (pintype "passive"))
      (node (ref "L4") (pin "1") (pinfunction "1_1") (pintype "passive"))
    )
    (net (code "31") (name "Net-(R25-Pad2)") (class "Default")
      (node (ref "R25") (pin "2") (pinfunction "2_2") (pintype "passive"))
      (node (ref "R26") (pin "3") (pintype "passive"))
    )
    (net (code "32") (name "Net-(R26-Pad1)") (class "Default")
      (node (ref "R26") (pin "1") (pintype "passive"))
      (node (ref "R27") (pin "1") (pinfunction "1_1") (pintype "passive"))
    )
    (net (code "33") (name "Net-(R28-Pad1)") (class "Default")
      (node (ref "R28") (pin "1") (pinfunction "1_1") (pintype "passive"))
      (node (ref "U11") (pin "3") (pinfunction "C_3") (pintype "passive"))
      (node (ref "U11") (pin "4") (pinfunction "D_4") (pintype "passive"))
    )
    (net (code "34") (name "Net-(U1-BOOT0)") (class "Default")
      (node (ref "R2") (pin "2") (pinfunction "2_2") (pintype "passive"))
      (node (ref "U1") (pin "60") (pinfunction "BOOT0_60") (pintype "input"))
    )
    (net (code "35") (name "Net-(U1-OSC_IN{slash}PD0)") (class "Default")
      (node (ref "U1") (pin "5") (pinfunction "OSC_IN/PD0_5") (pintype "input"))
      (node (ref "X1") (pin "1") (pinfunction "OSC1_1") (pintype "passive"))
    )
    (net (code "36") (name "Net-(U1-OSC_OUT{slash}PD1)") (class "Default")
      (node (ref "R1") (pin "2") (pinfunction "2_2") (pintype "passive"))
      (node (ref "U1") (pin "6") (pinfunction "OSC_OUT/PD1_6") (pintype "output"))
    )
    (net (code "37") (name "Net-(U1-PA1)") (class "Default")
      (node (ref "C11") (pin "1") (pinfunction "1_1") (pintype "passive"))
      (node (ref "R10") (pin "2") (pinfunction "2_2") (pintype "passive"))
      (node (ref "U1") (pin "15") (pinfunction "PA1_15") (pintype "bidirectional"))
    )
    (net (code "38") (name "Net-(U1-PA2)") (class "Default")
      (node (ref "C12") (pin "2") (pinfunction "2_2") (pintype "passive"))
      (node (ref "R11") (pin "2") (pinfunction "2_2") (pintype "passive"))
      (node (ref "U1") (pin "16") (pinfunction "PA2_16") (pintype "bidirectional"))
    )
    (net (code "39") (name "Net-(U1-PA3)") (class "Default")
      (node (ref "C13") (pin "2") (pinfunction "2_2") (pintype "passive"))
      (node (ref "R12") (pin "2") (pinfunction "2_2") (pintype "passive"))
      (node (ref "U1") (pin "17") (pinfunction "PA3_17") (pintype "bidirectional"))
    )
    (net (code "40") (name "Net-(U1-VDDA)") (class "Default")
      (node (ref "C6") (pin "2") (pinfunction "2_2") (pintype "passive"))
      (node (ref "C7") (pin "2") (pinfunction "2_2") (pintype "passive"))
      (node (ref "L6") (pin "2") (pinfunction "2_2") (pintype "passive"))
      (node (ref "U1") (pin "13") (pinfunction "VDDA_13") (pintype "power_in"))
    )
    (net (code "41") (name "Net-(U2-BP)") (class "Default")
      (node (ref "C21") (pin "2") (pinfunction "2_2") (pintype "passive"))
      (node (ref "U2") (pin "4") (pinfunction "BP_4") (pintype "passive"))
    )
    (net (code "42") (name "Net-(U4-BST)") (class "Default")
      (node (ref "C19") (pin "1") (pinfunction "1_1") (pintype "passive"))
      (node (ref "U4") (pin "8") (pinfunction "BST_8") (pintype "passive"))
    )
    (net (code "43") (name "Net-(U4-COMP)") (class "Default")
      (node (ref "C18") (pin "1") (pinfunction "1_1") (pintype "passive"))
      (node (ref "U4") (pin "3") (pinfunction "COMP_3") (pintype "passive"))
    )
    (net (code "44") (name "Net-(U4-FB)") (class "Default")
      (node (ref "R20") (pin "1") (pinfunction "1_1") (pintype "passive"))
      (node (ref "R21") (pin "2") (pinfunction "2_2") (pintype "passive"))
      (node (ref "U4") (pin "4") (pinfunction "FB_4") (pintype "passive"))
    )
    (net (code "45") (name "Net-(U4-FREQ)") (class "Default")
      (node (ref "R19") (pin "2") (pinfunction "2_2") (pintype "passive"))
      (node (ref "U4") (pin "6") (pinfunction "FREQ_6") (pintype "passive"))
    )
    (net (code "46") (name "Net-(U5-RFO)") (class "Default")
      (node (ref "C15") (pin "1") (pinfunction "1_1") (pintype "passive"))
      (node (ref "L1") (pin "1") (pinfunction "1_1") (pintype "passive"))
      (node (ref "U5") (pin "5") (pinfunction "RFO_5") (pintype "passive"))
    )
    (net (code "47") (name "Net-(U5-XTAL)") (class "Default")
      (node (ref "U5") (pin "1") (pinfunction "XTAL_1") (pintype "passive"))
      (node (ref "X2") (pin "1") (pintype "passive"))
    )
    (net (code "48") (name "Net-(U10-+IN)") (class "Default")
      (node (ref "R15") (pin "1") (pinfunction "1_1") (pintype "passive"))
      (node (ref "U10") (pin "1") (pinfunction "+IN_1") (pintype "passive"))
      (node (ref "U9") (pin "4") (pinfunction "B_4") (pintype "passive"))
      (node (ref "U9") (pin "6") (pinfunction "B_6") (pintype "passive"))
    )
    (net (code "49") (name "Net-(U12-+IN)") (class "Default")
      (node (ref "R26") (pin "2") (pintype "passive"))
      (node (ref "U12") (pin "1") (pinfunction "+IN_1") (pintype "passive"))
    )
    (net (code "50") (name "Net-(U12--IN)") (class "Default")
      (node (ref "C27") (pin "2") (pinfunction "2_2") (pintype "passive"))
      (node (ref "R28") (pin "2") (pinfunction "2_2") (pintype "passive"))
      (node (ref "R29") (pin "1") (pinfunction "1_1") (pintype "passive"))
      (node (ref "U12") (pin "3") (pinfunction "-IN_3") (pintype "passive"))
    )
    (net (code "51") (name "Net-(U13-BP)") (class "Default")
      (node (ref "C41") (pin "2") (pinfunction "2_2") (pintype "passive"))
      (node (ref "U13") (pin "4") (pinfunction "BP_4") (pintype "passive"))
    )
    (net (code "52") (name "Net-(X1-OSC2)") (class "Default")
      (node (ref "R1") (pin "1") (pinfunction "1_1") (pintype "passive"))
      (node (ref "X1") (pin "3") (pinfunction "OSC2_3") (pintype "passive"))
    )
    (net (code "53") (name "unconnected-(DLOAD-D--Pad2)") (class "Default")
      (node (ref "DLOAD") (pin "2") (pinfunction "D-_2") (pintype "passive"))
    )
    (net (code "54") (name "unconnected-(U1-NRST-Pad7)") (class "Default")
      (node (ref "U1") (pin "7") (pinfunction "NRST_7") (pintype "bidirectional"))
    )
    (net (code "55") (name "unconnected-(U1-PA0-WKUP-Pad14)") (class "Default")
      (node (ref "U1") (pin "14") (pinfunction "PA0-WKUP_14") (pintype "bidirectional"))
    )
    (net (code "56") (name "unconnected-(U1-PA4-Pad20)") (class "Default")
      (node (ref "U1") (pin "20") (pinfunction "PA4_20") (pintype "bidirectional"))
    )
    (net (code "57") (name "unconnected-(U1-PA5-Pad21)") (class "Default")
      (node (ref "U1") (pin "21") (pinfunction "PA5_21") (pintype "bidirectional"))
    )
    (net (code "58") (name "unconnected-(U1-PA6-Pad22)") (class "Default")
      (node (ref "U1") (pin "22") (pinfunction "PA6_22") (pintype "bidirectional"))
    )
    (net (code "59") (name "unconnected-(U1-PA7-Pad23)") (class "Default")
      (node (ref "U1") (pin "23") (pinfunction "PA7_23") (pintype "bidirectional"))
    )
    (net (code "60") (name "unconnected-(U1-PA8-Pad41)") (class "Default")
      (node (ref "U1") (pin "41") (pinfunction "PA8_41") (pintype "bidirectional"))
    )
    (net (code "61") (name "unconnected-(U1-PA9-Pad42)") (class "Default")
      (node (ref "U1") (pin "42") (pinfunction "PA9_42") (pintype "bidirectional"))
    )
    (net (code "62") (name "unconnected-(U1-PA10-Pad43)") (class "Default")
      (node (ref "U1") (pin "43") (pinfunction "PA10_43") (pintype "bidirectional"))
    )
    (net (code "63") (name "unconnected-(U1-PA11-Pad44)") (class "Default")
      (node (ref "U1") (pin "44") (pinfunction "PA11_44") (pintype "bidirectional"))
    )
    (net (code "64") (name "unconnected-(U1-PA12-Pad45)") (class "Default")
      (node (ref "U1") (pin "45") (pinfunction "PA12_45") (pintype "bidirectional"))
    )
    (net (code "65") (name "unconnected-(U1-PA15{slash}JTDI-Pad50)") (class "Default")
      (node (ref "U1") (pin "50") (pinfunction "PA15/JTDI_50") (pintype "bidirectional"))
    )
    (net (code "66") (name "unconnected-(U1-PB2{slash}BOOT1-Pad28)") (class "Default")
      (node (ref "U1") (pin "28") (pinfunction "PB2/BOOT1_28") (pintype "bidirectional"))
    )
    (net (code "67") (name "unconnected-(U1-PB3{slash}JTDO-Pad55)") (class "Default")
      (node (ref "U1") (pin "55") (pinfunction "PB3/JTDO_55") (pintype "bidirectional"))
    )
    (net (code "68") (name "unconnected-(U1-PB4{slash}JNTRST-Pad56)") (class "Default")
      (node (ref "U1") (pin "56") (pinfunction "PB4/JNTRST_56") (pintype "bidirectional"))
    )
    (net (code "69") (name "unconnected-(U1-PB5-Pad57)") (class "Default")
      (node (ref "U1") (pin "57") (pinfunction "PB5_57") (pintype "bidirectional"))
    )
    (net (code "70") (name "unconnected-(U1-PB7-Pad59)") (class "Default")
      (node (ref "U1") (pin "59") (pinfunction "PB7_59") (pintype "bidirectional"))
    )
    (net (code "71") (name "unconnected-(U1-PB8-Pad61)") (class "Default")
      (node (ref "U1") (pin "61") (pinfunction "PB8_61") (pintype "bidirectional"))
    )
    (net (code "72") (name "unconnected-(U1-PB9-Pad62)") (class "Default")
      (node (ref "U1") (pin "62") (pinfunction "PB9_62") (pintype "bidirectional"))
    )
    (net (code "73") (name "unconnected-(U1-PB14-Pad35)") (class "Default")
      (node (ref "U1") (pin "35") (pinfunction "PB14_35") (pintype "bidirectional"))
    )
    (net (code "74") (name "unconnected-(U1-PB15-Pad36)") (class "Default")
      (node (ref "U1") (pin "36") (pinfunction "PB15_36") (pintype "bidirectional"))
    )
    (net (code "75") (name "unconnected-(U1-PC0-Pad8)") (class "Default")
      (node (ref "U1") (pin "8") (pinfunction "PC0_8") (pintype "bidirectional"))
    )
    (net (code "76") (name "unconnected-(U1-PC1-Pad9)") (class "Default")
      (node (ref "U1") (pin "9") (pinfunction "PC1_9") (pintype "bidirectional"))
    )
    (net (code "77") (name "unconnected-(U1-PC2-Pad10)") (class "Default")
      (node (ref "U1") (pin "10") (pinfunction "PC2_10") (pintype "bidirectional"))
    )
    (net (code "78") (name "unconnected-(U1-PC3-Pad11)") (class "Default")
      (node (ref "U1") (pin "11") (pinfunction "PC3_11") (pintype "bidirectional"))
    )
    (net (code "79") (name "unconnected-(U1-PC4-Pad24)") (class "Default")
      (node (ref "U1") (pin "24") (pinfunction "PC4_24") (pintype "bidirectional"))
    )
    (net (code "80") (name "unconnected-(U1-PC5-Pad25)") (class "Default")
      (node (ref "U1") (pin "25") (pinfunction "PC5_25") (pintype "bidirectional"))
    )
    (net (code "81") (name "unconnected-(U1-PC6-Pad37)") (class "Default")
      (node (ref "U1") (pin "37") (pinfunction "PC6_37") (pintype "bidirectional"))
    )
    (net (code "82") (name "unconnected-(U1-PC7-Pad38)") (class "Default")
      (node (ref "U1") (pin "38") (pinfunction "PC7_38") (pintype "bidirectional"))
    )
    (net (code "83") (name "unconnected-(U1-PC8-Pad39)") (class "Default")
      (node (ref "U1") (pin "39") (pinfunction "PC8_39") (pintype "bidirectional"))
    )
    (net (code "84") (name "unconnected-(U1-PC9-Pad40)") (class "Default")
      (node (ref "U1") (pin "40") (pinfunction "PC9_40") (pintype "bidirectional"))
    )
    (net (code "85") (name "unconnected-(U1-PC10-Pad51)") (class "Default")
      (node (ref "U1") (pin "51") (pinfunction "PC10_51") (pintype "bidirectional"))
    )
    (net (code "86") (name "unconnected-(U1-PC11-Pad52)") (class "Default")
      (node (ref "U1") (pin "52") (pinfunction "PC11_52") (pintype "bidirectional"))
    )
    (net (code "87") (name "unconnected-(U1-PC12-Pad53)") (class "Default")
      (node (ref "U1") (pin "53") (pinfunction "PC12_53") (pintype "bidirectional"))
    )
    (net (code "88") (name "unconnected-(U1-PC15-OSC32_OUT-Pad4)") (class "Default")
      (node (ref "U1") (pin "4") (pinfunction "PC15-OSC32_OUT_4") (pintype "bidirectional"))
    )
    (net (code "89") (name "unconnected-(U1-PD2-Pad54)") (class "Default")
      (node (ref "U1") (pin "54") (pinfunction "PD2_54") (pintype "bidirectional"))
    )
    (net (code "90") (name "unconnected-(U1-VBAT-Pad1)") (class "Default")
      (node (ref "U1") (pin "1") (pinfunction "VBAT_1") (pintype "power_in"))
    )
    (net (code "91") (name "unconnected-(U4-EN-Pad2)") (class "Default")
      (node (ref "U4") (pin "2") (pinfunction "EN_2") (pintype "passive"))
    )
    (net (code "92") (name "unconnected-(U8-NC-Pad3)") (class "Default")
      (node (ref "U8") (pin "3") (pinfunction "NC_3") (pintype "passive"))
    )
    (net (code "93") (name "unconnected-(U8-NC-Pad4)") (class "Default")
      (node (ref "U8") (pin "4") (pinfunction "NC_4") (pintype "passive"))
    )
  )
)
